# MAX31855_arduino.net
KiCad netlist of a schematic drawn in EAGLE
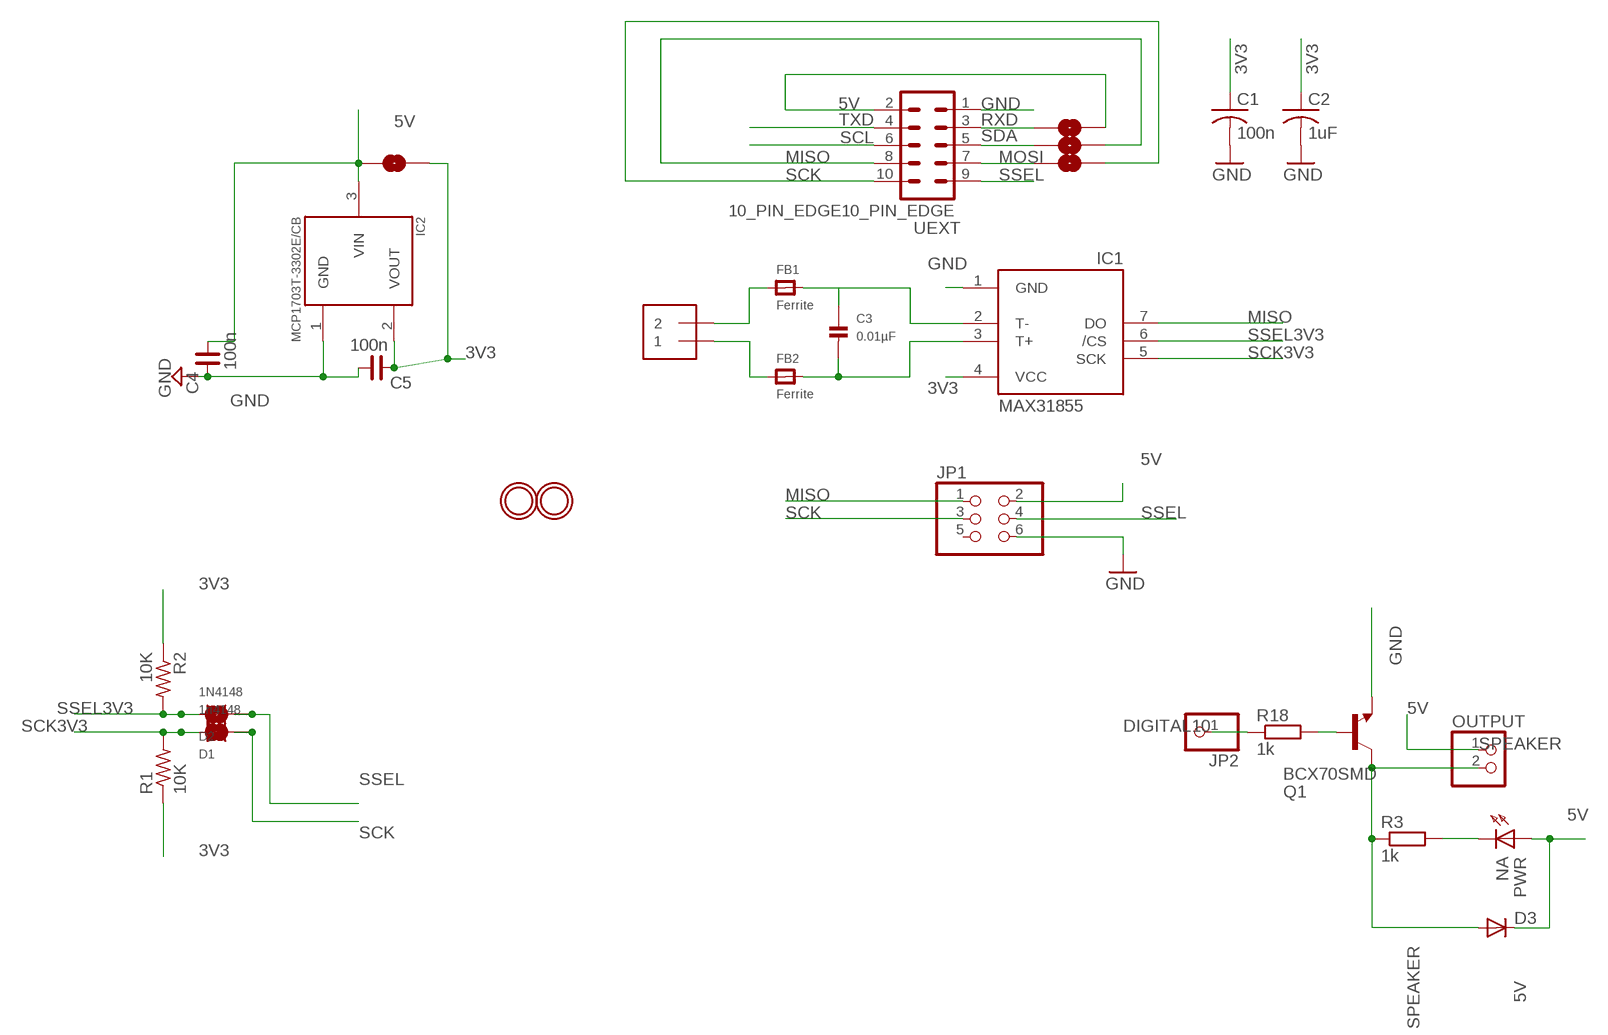
[diagram p0: schematic, sheet 1]

(export (version "E")
  (design (tool "Eeschema 10.0.6"))
  (components
    (comp (ref "3V3")
      (value "SOLDERJUMPERNO")
      (footprint "eagle-import:SJ_2S-NO")
      (libsource (lib "eagle-import") (part "SOLDERJUMPERNO"))
    )
    (comp (ref "C1")
      (value "100n")
      (footprint "eagle-import:C0805K")
      (libsource (lib "eagle-import") (part "C-USC0805K"))
    )
    (comp (ref "C2")
      (value "1uF")
      (footprint "eagle-import:C0805K")
      (libsource (lib "eagle-import") (part "C-USC0805K"))
    )
    (comp (ref "C3")
      (value "0.01µF")
      (footprint "eagle-import:_0805")
      (libsource (lib "eagle-import") (part "CAP_CERAMIC_0805"))
    )
    (comp (ref "C4")
      (value "100n")
      (footprint "eagle-import:C0603")
      (libsource (lib "eagle-import") (part "C_0603"))
    )
    (comp (ref "C5")
      (value "100n")
      (footprint "eagle-import:C0603")
      (libsource (lib "eagle-import") (part "C_0603"))
    )
    (comp (ref "D1")
      (value "1n4148")
      (footprint "eagle-import:SOD-323F")
      (libsource (lib "eagle-import") (part "DIODESOD-323F"))
    )
    (comp (ref "D2")
      (value "1N4148")
      (footprint "eagle-import:SOD-323F")
      (libsource (lib "eagle-import") (part "DIODESOD-323F"))
    )
    (comp (ref "D3")
      (value "DIODESOD")
      (footprint "eagle-import:SOD-323")
      (libsource (lib "eagle-import") (part "DIODESOD"))
    )
    (comp (ref "FB1")
      (value "Ferrite")
      (footprint "eagle-import:_0805")
      (libsource (lib "eagle-import") (part "FERRITE_0805"))
    )
    (comp (ref "FB2")
      (value "Ferrite")
      (footprint "eagle-import:_0805")
      (libsource (lib "eagle-import") (part "FERRITE_0805"))
    )
    (comp (ref "IC1")
      (value "MAX31855")
      (footprint "eagle-import:SO08")
      (libsource (lib "eagle-import") (part "MAX6675"))
    )
    (comp (ref "IC2")
      (value "MCP1703T-3302E/CB")
      (footprint "eagle-import:SOT23")
      (libsource (lib "eagle-import") (part "MCP1700T"))
    )
    (comp (ref "J1")
      (value "1X2-3.5MM")
      (footprint "eagle-import:1X2-3.5MM")
      (libsource (lib "eagle-import") (part "1X2-3.5MM"))
    )
    (comp (ref "JP1")
      (value "PINHD-2X3")
      (footprint "eagle-import:2X03")
      (libsource (lib "eagle-import") (part "PINHD-2X3"))
    )
    (comp (ref "JP2")
      (value "PINHD-1X1")
      (footprint "eagle-import:1X01")
      (libsource (lib "eagle-import") (part "PINHD-1X1"))
    )
    (comp (ref "MISO")
      (value "SOLDERJUMPERNO")
      (footprint "eagle-import:SJ_2S-NO")
      (libsource (lib "eagle-import") (part "SOLDERJUMPERNO"))
    )
    (comp (ref "OUTPUT")
      (value "PINHD-1X2")
      (footprint "eagle-import:1X02")
      (libsource (lib "eagle-import") (part "PINHD-1X2"))
    )
    (comp (ref "PWR")
      (value "NA")
      (footprint "eagle-import:LED-0603")
      (libsource (lib "eagle-import") (part "LED0603DWS"))
    )
    (comp (ref "Q1")
      (value "BCX70SMD")
      (footprint "eagle-import:SOT23")
      (libsource (lib "eagle-import") (part "BCX70SMD"))
    )
    (comp (ref "R1")
      (value "10K")
      (footprint "eagle-import:R0603")
      (libsource (lib "eagle-import") (part "R-US_R0603"))
    )
    (comp (ref "R2")
      (value "10K")
      (footprint "eagle-import:R0603")
      (libsource (lib "eagle-import") (part "R-US_R0603"))
    )
    (comp (ref "R3")
      (value "1k")
      (footprint "eagle-import:R0603")
      (libsource (lib "eagle-import") (part "R-EU_R0603"))
    )
    (comp (ref "R18")
      (value "1k")
      (footprint "eagle-import:R0603")
      (libsource (lib "eagle-import") (part "R-EU_R0603"))
    )
    (comp (ref "SCK")
      (value "SOLDERJUMPERNO")
      (footprint "eagle-import:SJ_2S-NO")
      (libsource (lib "eagle-import") (part "SOLDERJUMPERNO"))
    )
    (comp (ref "SCK1")
      (value "SOLDERJUMPERNO")
      (footprint "eagle-import:SJ_2S-NO")
      (libsource (lib "eagle-import") (part "SOLDERJUMPERNO"))
    )
    (comp (ref "SCK2")
      (value "SOLDERJUMPERNO")
      (footprint "eagle-import:SJ_2S-NO")
      (libsource (lib "eagle-import") (part "SOLDERJUMPERNO"))
    )
    (comp (ref "SCK3")
      (value "SOLDERJUMPERNO")
      (footprint "eagle-import:SJ_2S-NO")
      (libsource (lib "eagle-import") (part "SOLDERJUMPERNO"))
    )
    (comp (ref "U$3")
      (value "10_PIN_EDGE10_PIN_EDGE")
      (footprint "eagle-import:10_PIN_EDGE")
      (libsource (lib "eagle-import") (part "10_PIN_EDGE10_PIN_EDGE"))
    )
    (comp (ref "U$4")
      (value "MOUNTINGHOLE2.0")
      (footprint "eagle-import:MOUNTINGHOLE_2.0_PLATED")
      (libsource (lib "eagle-import") (part "MOUNTINGHOLE2.0"))
    )
    (comp (ref "U$5")
      (value "MOUNTINGHOLE2.0")
      (footprint "eagle-import:MOUNTINGHOLE_2.0_PLATED")
      (libsource (lib "eagle-import") (part "MOUNTINGHOLE2.0"))
    )
  )
  (nets
    (net (code "1") (name "/3V3") (class "Default")
      (node (ref "C1") (pin "1") (pinfunction "1_1") (pintype "passive"))
      (node (ref "C2") (pin "1") (pinfunction "1_1") (pintype "passive"))
      (node (ref "C5") (pin "2") (pinfunction "2_2") (pintype "passive"))
      (node (ref "IC1") (pin "4") (pinfunction "VCC_4") (pintype "power_in"))
      (node (ref "IC2") (pin "2") (pinfunction "VOUT_2") (pintype "bidirectional"))
      (node (ref "R1") (pin "1") (pinfunction "1_1") (pintype "passive"))
      (node (ref "R2") (pin "1") (pinfunction "1_1") (pintype "passive"))
      (node (ref "SCK3") (pin "1") (pinfunction "1_1") (pintype "passive"))
    )
    (net (code "2") (name "/5V") (class "Default")
      (node (ref "3V3") (pin "2") (pinfunction "2_2") (pintype "passive"))
      (node (ref "C4") (pin "1") (pinfunction "1_1") (pintype "passive"))
      (node (ref "D3") (pin "1") (pinfunction "C_1") (pintype "passive"))
      (node (ref "IC2") (pin "3") (pinfunction "VIN_3") (pintype "bidirectional"))
      (node (ref "JP1") (pin "2") (pinfunction "2_2") (pintype "passive"))
      (node (ref "OUTPUT") (pin "1") (pinfunction "1_1") (pintype "passive"))
      (node (ref "PWR") (pin "A") (pinfunction "A_A") (pintype "passive"))
      (node (ref "SCK3") (pin "2") (pinfunction "2_2") (pintype "passive"))
      (node (ref "U$3") (pin "2") (pinfunction "2_2") (pintype "passive"))
    )
    (net (code "3") (name "/DIGITAL10") (class "Default")
      (node (ref "JP2") (pin "1") (pinfunction "1_1") (pintype "passive"))
      (node (ref "R18") (pin "1") (pinfunction "1_1") (pintype "passive"))
    )
    (net (code "4") (name "/MISO") (class "Default")
      (node (ref "IC1") (pin "7") (pinfunction "DO_7") (pintype "output"))
      (node (ref "JP1") (pin "1") (pinfunction "1_1") (pintype "passive"))
      (node (ref "MISO") (pin "2") (pinfunction "2_2") (pintype "passive"))
      (node (ref "U$3") (pin "8") (pinfunction "8_8") (pintype "passive"))
    )
    (net (code "5") (name "/MOSI") (class "Default")
      (node (ref "SCK") (pin "1") (pinfunction "1_1") (pintype "passive"))
      (node (ref "U$3") (pin "7") (pinfunction "7_7") (pintype "passive"))
    )
    (net (code "6") (name "/RXD") (class "Default")
      (node (ref "3V3") (pin "1") (pinfunction "1_1") (pintype "passive"))
      (node (ref "U$3") (pin "3") (pinfunction "3_3") (pintype "passive"))
    )
    (net (code "7") (name "/SCK") (class "Default")
      (node (ref "D1") (pin "C") (pinfunction "C_C") (pintype "passive"))
      (node (ref "JP1") (pin "3") (pinfunction "3_3") (pintype "passive"))
      (node (ref "SCK") (pin "2") (pinfunction "2_2") (pintype "passive"))
      (node (ref "SCK2") (pin "2") (pinfunction "2_2") (pintype "passive"))
      (node (ref "U$3") (pin "10") (pinfunction "10_10") (pintype "passive"))
    )
    (net (code "8") (name "/SCK3V3") (class "Default")
      (node (ref "D1") (pin "A") (pinfunction "A_A") (pintype "passive"))
      (node (ref "IC1") (pin "5") (pinfunction "SCK_5") (pintype "input"))
      (node (ref "R1") (pin "2") (pinfunction "2_2") (pintype "passive"))
      (node (ref "SCK2") (pin "1") (pinfunction "1_1") (pintype "passive"))
    )
    (net (code "9") (name "/SCL") (class "Default")
      (node (ref "U$3") (pin "6") (pinfunction "6_6") (pintype "passive"))
    )
    (net (code "10") (name "/SDA") (class "Default")
      (node (ref "MISO") (pin "1") (pinfunction "1_1") (pintype "passive"))
      (node (ref "U$3") (pin "5") (pinfunction "5_5") (pintype "passive"))
    )
    (net (code "11") (name "/SPEAKER") (class "Default")
      (node (ref "D3") (pin "2") (pinfunction "A_2") (pintype "passive"))
      (node (ref "OUTPUT") (pin "2") (pinfunction "2_2") (pintype "passive"))
      (node (ref "Q1") (pin "3") (pinfunction "C_3") (pintype "passive"))
      (node (ref "R3") (pin "1") (pinfunction "1_1") (pintype "passive"))
    )
    (net (code "12") (name "/SSEL") (class "Default")
      (node (ref "D2") (pin "C") (pinfunction "C_C") (pintype "passive"))
      (node (ref "JP1") (pin "4") (pinfunction "4_4") (pintype "passive"))
      (node (ref "SCK1") (pin "2") (pinfunction "2_2") (pintype "passive"))
      (node (ref "U$3") (pin "9") (pinfunction "9_9") (pintype "passive"))
    )
    (net (code "13") (name "/SSEL3V3") (class "Default")
      (node (ref "D2") (pin "A") (pinfunction "A_A") (pintype "passive"))
      (node (ref "IC1") (pin "6") (pinfunction "/CS_6") (pintype "input"))
      (node (ref "R2") (pin "2") (pinfunction "2_2") (pintype "passive"))
      (node (ref "SCK1") (pin "1") (pinfunction "1_1") (pintype "passive"))
    )
    (net (code "14") (name "/TXD") (class "Default")
      (node (ref "U$3") (pin "4") (pinfunction "4_4") (pintype "passive"))
    )
    (net (code "15") (name "GND") (class "Default")
      (node (ref "C1") (pin "2") (pinfunction "2_2") (pintype "passive"))
      (node (ref "C2") (pin "2") (pinfunction "2_2") (pintype "passive"))
      (node (ref "C4") (pin "2") (pinfunction "2_2") (pintype "passive"))
      (node (ref "C5") (pin "1") (pinfunction "1_1") (pintype "passive"))
      (node (ref "IC1") (pin "1") (pinfunction "GND_1") (pintype "power_in"))
      (node (ref "IC2") (pin "1") (pinfunction "GND_1") (pintype "bidirectional"))
      (node (ref "JP1") (pin "6") (pinfunction "6_6") (pintype "passive"))
      (node (ref "Q1") (pin "2") (pinfunction "E_2") (pintype "passive"))
      (node (ref "U$3") (pin "1") (pinfunction "1_1") (pintype "passive"))
    )
    (net (code "16") (name "Net-(C3-P$1)") (class "Default")
      (node (ref "C3") (pin "1") (pinfunction "P$1_1") (pintype "passive"))
      (node (ref "FB1") (pin "2") (pinfunction "P$2_2") (pintype "passive"))
      (node (ref "IC1") (pin "2") (pinfunction "T-_2") (pintype "input"))
    )
    (net (code "17") (name "Net-(C3-P$2)") (class "Default")
      (node (ref "C3") (pin "2") (pinfunction "P$2_2") (pintype "passive"))
      (node (ref "FB2") (pin "2") (pinfunction "P$2_2") (pintype "passive"))
      (node (ref "IC1") (pin "3") (pinfunction "T+_3") (pintype "input"))
    )
    (net (code "18") (name "Net-(FB1-P$1)") (class "Default")
      (node (ref "FB1") (pin "1") (pinfunction "P$1_1") (pintype "passive"))
      (node (ref "J1") (pin "2") (pinfunction "2_2") (pintype "passive"))
    )
    (net (code "19") (name "Net-(FB2-P$1)") (class "Default")
      (node (ref "FB2") (pin "1") (pinfunction "P$1_1") (pintype "passive"))
      (node (ref "J1") (pin "1") (pinfunction "1_1") (pintype "passive"))
    )
    (net (code "20") (name "Net-(PWR-PadC)") (class "Default")
      (node (ref "PWR") (pin "C") (pinfunction "C_C") (pintype "passive"))
      (node (ref "R3") (pin "2") (pinfunction "2_2") (pintype "passive"))
    )
    (net (code "21") (name "Net-(Q1-B)") (class "Default")
      (node (ref "Q1") (pin "1") (pinfunction "B_1") (pintype "passive"))
      (node (ref "R18") (pin "2") (pinfunction "2_2") (pintype "passive"))
    )
    (net (code "22") (name "unconnected-(JP1-Pad5)") (class "Default")
      (node (ref "JP1") (pin "5") (pinfunction "5_5") (pintype "passive"))
    )
  )
)
